# half-pint-turbidimeter_power.net
KiCad netlist of a schematic drawn in EAGLE
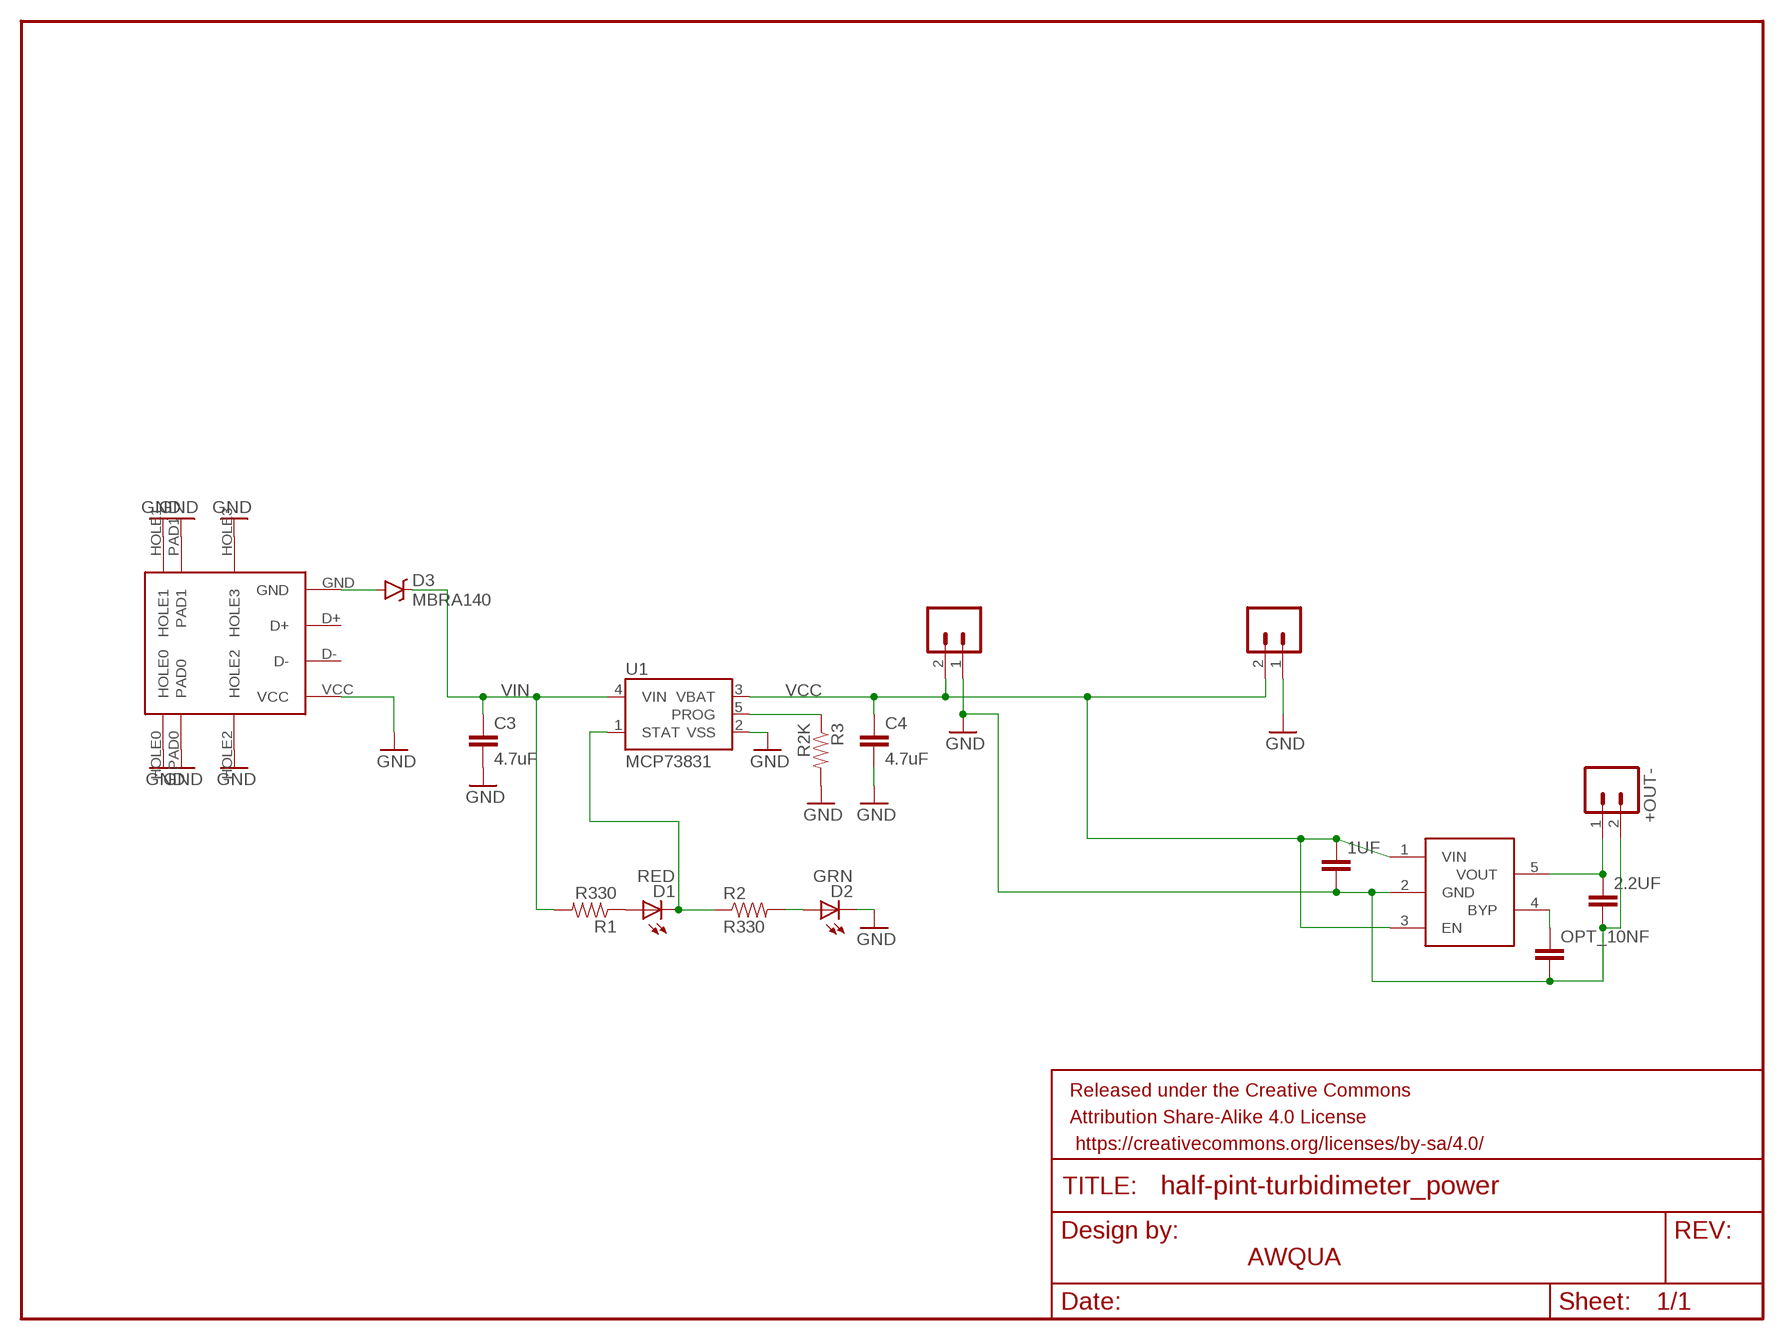
[diagram p0: schematic, sheet 1]

(export (version "E")
  (design (tool "Eeschema 10.0.6"))
  (components
    (comp (ref "+OUT-")
      (value "M02PTH")
      (footprint "eagle-import:1X02")
      (libsource (lib "eagle-import") (part "SparkFun-Connectors_M02PTH"))
    )
    (comp (ref "1UF")
      (value "CAP0603-CAP")
      (footprint "eagle-import:0603-CAP")
      (libsource (lib "eagle-import") (part "SparkFun-Passives_CAP0603-CAP"))
    )
    (comp (ref "2.2UF")
      (value "CAP0603-CAP")
      (footprint "eagle-import:0603-CAP")
      (libsource (lib "eagle-import") (part "SparkFun-Passives_CAP0603-CAP"))
    )
    (comp (ref "C3")
      (value "4.7uF")
      (footprint "eagle-import:0402-CAP")
      (libsource (lib "eagle-import") (part "CAP0402-CAP"))
    )
    (comp (ref "C4")
      (value "4.7uF")
      (footprint "eagle-import:0402-CAP")
      (libsource (lib "eagle-import") (part "CAP0402-CAP"))
    )
    (comp (ref "D1")
      (value "RED")
      (footprint "eagle-import:LED-0603")
      (libsource (lib "eagle-import") (part "LED0603"))
    )
    (comp (ref "D2")
      (value "GRN")
      (footprint "eagle-import:LED-0603")
      (libsource (lib "eagle-import") (part "LED0603"))
    )
    (comp (ref "D3")
      (value "MBRA140")
      (footprint "eagle-import:SMA-DIODE")
      (libsource (lib "eagle-import") (part "MBRA140"))
    )
    (comp (ref "FRAME1")
      (value "FRAME-LETTER")
      (footprint "eagle-import:CREATIVE_COMMONS")
      (libsource (lib "eagle-import") (part "FRAME-LETTER"))
    )
    (comp (ref "JMP")
      (value "M02PTH")
      (footprint "eagle-import:1X02")
      (libsource (lib "eagle-import") (part "M02PTH"))
    )
    (comp (ref "JP7")
      (value "LiPo Battery")
      (footprint "eagle-import:JST-2-SMD")
      (libsource (lib "eagle-import") (part "M02-JST-2MM-SMT"))
    )
    (comp (ref "OPT_10NF")
      (value "CAP0603-CAP")
      (footprint "eagle-import:0603-CAP")
      (libsource (lib "eagle-import") (part "SparkFun-Passives_CAP0603-CAP"))
    )
    (comp (ref "R1")
      (value "R330")
      (footprint "eagle-import:0402-RES")
      (libsource (lib "eagle-import") (part "RESISTOR0402-RES"))
    )
    (comp (ref "R2")
      (value "R330")
      (footprint "eagle-import:0402-RES")
      (libsource (lib "eagle-import") (part "RESISTOR0402-RES"))
    )
    (comp (ref "R3")
      (value "R2K")
      (footprint "eagle-import:0402-RES")
      (libsource (lib "eagle-import") (part "RESISTOR0402-RES"))
    )
    (comp (ref "U$2")
      (value "LP2985")
      (footprint "eagle-import:LP2985")
      (libsource (lib "eagle-import") (part "LP2985"))
    )
    (comp (ref "U$3")
      (value "USBMICRO-DX4R005JJ2")
      (footprint "eagle-import:USBMICRO-DX4R005JJ2")
      (libsource (lib "eagle-import") (part "USBMICRO-DX4R005JJ2"))
    )
    (comp (ref "U1")
      (value "MCP73831")
      (footprint "eagle-import:SOT23-5")
      (libsource (lib "eagle-import") (part "MCP73831"))
    )
  )
  (nets
    (net (code "1") (name "/VCC") (class "Default")
      (node (ref "1UF") (pin "1") (pinfunction "1_1") (pintype "passive"))
      (node (ref "C4") (pin "1") (pinfunction "1_1") (pintype "passive"))
      (node (ref "JMP") (pin "2") (pinfunction "2_2") (pintype "passive"))
      (node (ref "JP7") (pin "2") (pinfunction "2_2") (pintype "passive"))
      (node (ref "U$2") (pin "1") (pinfunction "VIN_1") (pintype "bidirectional"))
      (node (ref "U$2") (pin "3") (pinfunction "EN_3") (pintype "bidirectional"))
      (node (ref "U1") (pin "3") (pinfunction "VBAT_3") (pintype "power_in"))
    )
    (net (code "2") (name "/VIN") (class "Default")
      (node (ref "C3") (pin "1") (pinfunction "1_1") (pintype "passive"))
      (node (ref "D3") (pin "C") (pinfunction "C_C") (pintype "passive"))
      (node (ref "R1") (pin "2") (pinfunction "2_2") (pintype "passive"))
      (node (ref "U1") (pin "4") (pinfunction "VIN_4") (pintype "power_in"))
    )
    (net (code "3") (name "GND") (class "Default")
      (node (ref "+OUT-") (pin "2") (pinfunction "2_2") (pintype "passive"))
      (node (ref "1UF") (pin "2") (pinfunction "2_2") (pintype "passive"))
      (node (ref "2.2UF") (pin "2") (pinfunction "2_2") (pintype "passive"))
      (node (ref "C3") (pin "2") (pinfunction "2_2") (pintype "passive"))
      (node (ref "C4") (pin "2") (pinfunction "2_2") (pintype "passive"))
      (node (ref "D2") (pin "C") (pinfunction "C_C") (pintype "passive"))
      (node (ref "JMP") (pin "1") (pinfunction "1_1") (pintype "passive"))
      (node (ref "JP7") (pin "1") (pinfunction "1_1") (pintype "passive"))
      (node (ref "OPT_10NF") (pin "2") (pinfunction "2_2") (pintype "passive"))
      (node (ref "R3") (pin "2") (pinfunction "2_2") (pintype "passive"))
      (node (ref "U$2") (pin "2") (pinfunction "GND_2") (pintype "bidirectional"))
      (node (ref "U$3") (pin "HOLE0") (pinfunction "HOLE0_HOLE0") (pintype "bidirectional"))
      (node (ref "U$3") (pin "HOLE1") (pinfunction "HOLE1_HOLE1") (pintype "bidirectional"))
      (node (ref "U$3") (pin "HOLE2") (pinfunction "HOLE2_HOLE2") (pintype "bidirectional"))
      (node (ref "U$3") (pin "HOLE3") (pinfunction "HOLE3_HOLE3") (pintype "bidirectional"))
      (node (ref "U$3") (pin "PAD0") (pinfunction "PAD0_PAD0") (pintype "bidirectional"))
      (node (ref "U$3") (pin "PAD1") (pinfunction "PAD1_PAD1") (pintype "bidirectional"))
      (node (ref "U$3") (pin "VCC") (pinfunction "VCC_VCC") (pintype "bidirectional"))
      (node (ref "U1") (pin "2") (pinfunction "VSS_2") (pintype "power_in"))
    )
    (net (code "4") (name "Net-(D1-PadA)") (class "Default")
      (node (ref "D1") (pin "A") (pinfunction "A_A") (pintype "passive"))
      (node (ref "R1") (pin "1") (pinfunction "1_1") (pintype "passive"))
    )
    (net (code "5") (name "Net-(D2-PadA)") (class "Default")
      (node (ref "D2") (pin "A") (pinfunction "A_A") (pintype "passive"))
      (node (ref "R2") (pin "2") (pinfunction "2_2") (pintype "passive"))
    )
    (net (code "6") (name "Net-(D3-PadA)") (class "Default")
      (node (ref "D3") (pin "A") (pinfunction "A_A") (pintype "passive"))
      (node (ref "U$3") (pin "GND") (pinfunction "GND_GND") (pintype "bidirectional"))
    )
    (net (code "7") (name "Net-(U$2-BYP)") (class "Default")
      (node (ref "OPT_10NF") (pin "1") (pinfunction "1_1") (pintype "passive"))
      (node (ref "U$2") (pin "4") (pinfunction "BYP_4") (pintype "bidirectional"))
    )
    (net (code "8") (name "Net-(U$2-VOUT)") (class "Default")
      (node (ref "+OUT-") (pin "1") (pinfunction "1_1") (pintype "passive"))
      (node (ref "2.2UF") (pin "1") (pinfunction "1_1") (pintype "passive"))
      (node (ref "U$2") (pin "5") (pinfunction "VOUT_5") (pintype "bidirectional"))
    )
    (net (code "9") (name "Net-(U1-PROG)") (class "Default")
      (node (ref "R3") (pin "1") (pinfunction "1_1") (pintype "passive"))
      (node (ref "U1") (pin "5") (pinfunction "PROG_5") (pintype "input"))
    )
    (net (code "10") (name "Net-(U1-STAT)") (class "Default")
      (node (ref "D1") (pin "C") (pinfunction "C_C") (pintype "passive"))
      (node (ref "R2") (pin "1") (pinfunction "1_1") (pintype "passive"))
      (node (ref "U1") (pin "1") (pinfunction "STAT_1") (pintype "output"))
    )
    (net (code "11") (name "unconnected-(U$3-PadD+)") (class "Default")
      (node (ref "U$3") (pin "D+") (pinfunction "D+_D+") (pintype "bidirectional"))
    )
    (net (code "12") (name "unconnected-(U$3-PadD-)") (class "Default")
      (node (ref "U$3") (pin "D-") (pinfunction "D-_D-") (pintype "bidirectional"))
    )
  )
)
